# tvac_systems_interface.net
KiCad netlist of a schematic drawn in EAGLE
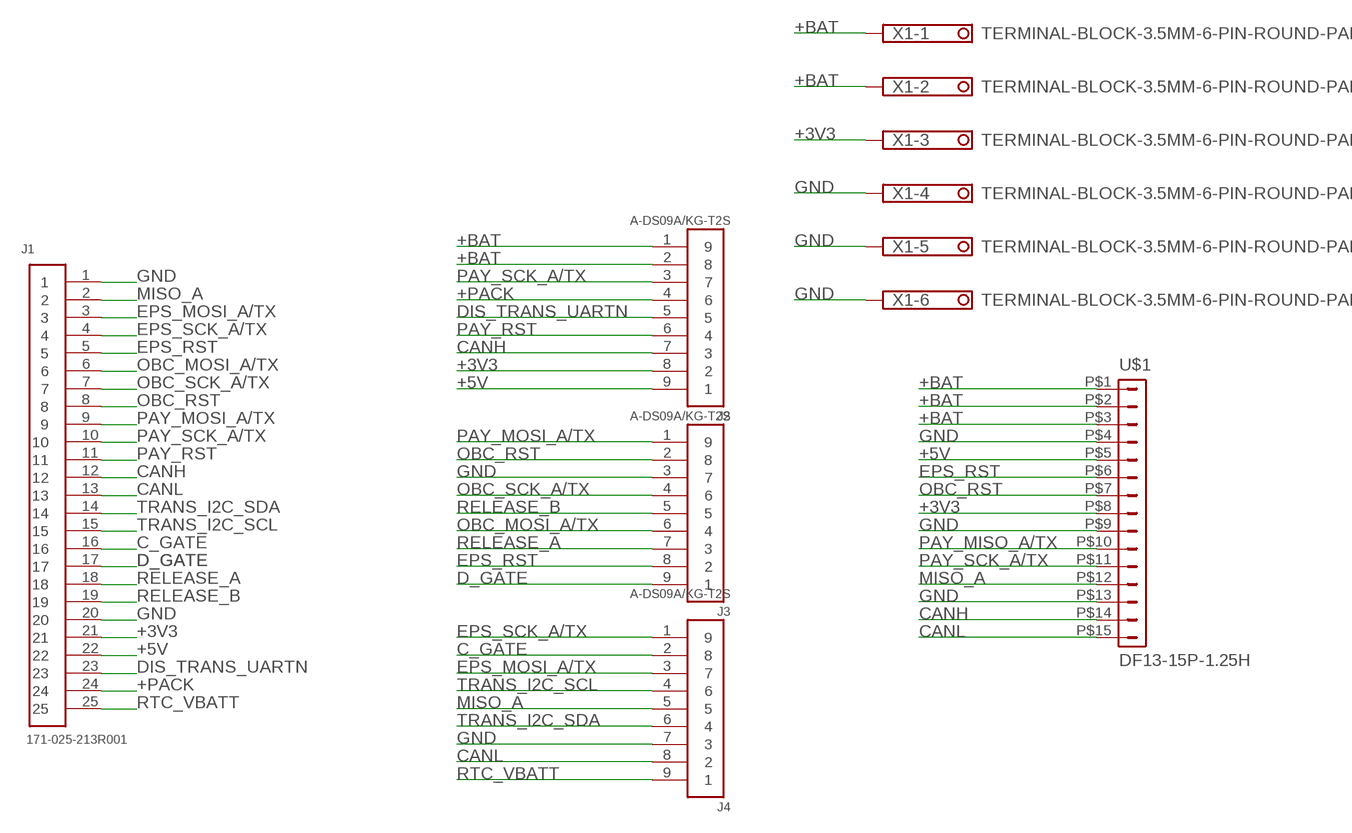
[diagram p0: schematic, sheet 1]

(export (version "E")
  (design (tool "Eeschema 10.0.6"))
  (components
    (comp (ref "J1")
      (value "171-025-213R001")
      (footprint "eagle-import:171-025-213R001")
      (fields
        (field (name "DIGIKEY_PART_NO") "4225FE-ND")
        (field (name "MANUFACTURER") "NorComp Inc.")
        (field (name "CREATED_BY") "PCBLayout.com")
      )
      (libsource (lib "eagle-import") (part "171-025-213R001"))
    )
    (comp (ref "J2")
      (value "A-DS09A/KG-T2S")
      (footprint "eagle-import:A-DS09A_KG-T2S")
      (fields
        (field (name "DIGI_KEY_PART_NUMBER") "AE10968-ND")
        (field (name "MANUFACTURER") "Assmann WSW Components")
        (field (name "MPN") "A-DS 09 A/KG-T2S")
        (field (name "CREATEDBY") "PCBLayout.com")
      )
      (libsource (lib "eagle-import") (part "A-DS09A/KG-T2S"))
    )
    (comp (ref "J3")
      (value "A-DS09A/KG-T2S")
      (footprint "eagle-import:A-DS09A_KG-T2S")
      (fields
        (field (name "DIGI_KEY_PART_NUMBER") "AE10968-ND")
        (field (name "MANUFACTURER") "Assmann WSW Components")
        (field (name "MPN") "A-DS 09 A/KG-T2S")
        (field (name "CREATEDBY") "PCBLayout.com")
      )
      (libsource (lib "eagle-import") (part "A-DS09A/KG-T2S"))
    )
    (comp (ref "J4")
      (value "A-DS09A/KG-T2S")
      (footprint "eagle-import:A-DS09A_KG-T2S")
      (fields
        (field (name "DIGI_KEY_PART_NUMBER") "AE10968-ND")
        (field (name "MANUFACTURER") "Assmann WSW Components")
        (field (name "MPN") "A-DS 09 A/KG-T2S")
        (field (name "CREATEDBY") "PCBLayout.com")
      )
      (libsource (lib "eagle-import") (part "A-DS09A/KG-T2S"))
    )
    (comp (ref "U$1")
      (value "DF13-15P-1.25H")
      (footprint "eagle-import:DF13A-15P-1.25H")
      (libsource (lib "eagle-import") (part "DF13-15P-1.25H"))
    )
    (comp (ref "X1")
      (value "TERMINAL-BLOCK-3.5MM-6-PIN-ROUND-PAD")
      (footprint "eagle-import:TERMINAL-BLOCK-6-PIN-3.5MM-ROUND-PAD")
      (libsource (lib "eagle-import") (part "TERMINAL-BLOCK-3.5MM-6-PIN-ROUND-PAD"))
    )
  )
  (nets
    (net (code "1") (name "/+3V3") (class "Default")
      (node (ref "J1") (pin "21") (pinfunction "21_21") (pintype "passive"))
      (node (ref "J2") (pin "8") (pinfunction "2_8") (pintype "passive"))
      (node (ref "U$1") (pin "P$8") (pinfunction "8_P$8") (pintype "passive"))
      (node (ref "X1") (pin "3") (pinfunction "K_3") (pintype "passive"))
    )
    (net (code "2") (name "/+5V") (class "Default")
      (node (ref "J1") (pin "22") (pinfunction "22_22") (pintype "passive"))
      (node (ref "J2") (pin "9") (pinfunction "1_9") (pintype "passive"))
      (node (ref "U$1") (pin "P$5") (pinfunction "5_P$5") (pintype "passive"))
    )
    (net (code "3") (name "/+BAT") (class "Default")
      (node (ref "J2") (pin "1") (pinfunction "9_1") (pintype "passive"))
      (node (ref "J2") (pin "2") (pinfunction "8_2") (pintype "passive"))
      (node (ref "U$1") (pin "P$1") (pinfunction "1_P$1") (pintype "passive"))
      (node (ref "U$1") (pin "P$2") (pinfunction "2_P$2") (pintype "passive"))
      (node (ref "U$1") (pin "P$3") (pinfunction "3_P$3") (pintype "passive"))
      (node (ref "X1") (pin "1") (pinfunction "K_1") (pintype "passive"))
      (node (ref "X1") (pin "2") (pinfunction "K_2") (pintype "passive"))
    )
    (net (code "4") (name "/+PACK") (class "Default")
      (node (ref "J1") (pin "24") (pinfunction "24_24") (pintype "passive"))
      (node (ref "J2") (pin "4") (pinfunction "6_4") (pintype "passive"))
    )
    (net (code "5") (name "/CANH") (class "Default")
      (node (ref "J1") (pin "12") (pinfunction "12_12") (pintype "passive"))
      (node (ref "J2") (pin "7") (pinfunction "3_7") (pintype "passive"))
      (node (ref "U$1") (pin "P$14") (pinfunction "14_P$14") (pintype "passive"))
    )
    (net (code "6") (name "/CANL") (class "Default")
      (node (ref "J1") (pin "13") (pinfunction "13_13") (pintype "passive"))
      (node (ref "J4") (pin "8") (pinfunction "2_8") (pintype "passive"))
      (node (ref "U$1") (pin "P$15") (pinfunction "15_P$15") (pintype "passive"))
    )
    (net (code "7") (name "/C_GATE") (class "Default")
      (node (ref "J1") (pin "16") (pinfunction "16_16") (pintype "passive"))
      (node (ref "J4") (pin "2") (pinfunction "8_2") (pintype "passive"))
    )
    (net (code "8") (name "/DIS_TRANS_UARTN") (class "Default")
      (node (ref "J1") (pin "23") (pinfunction "23_23") (pintype "passive"))
      (node (ref "J2") (pin "5") (pinfunction "5_5") (pintype "passive"))
    )
    (net (code "9") (name "/D_GATE") (class "Default")
      (node (ref "J1") (pin "17") (pinfunction "17_17") (pintype "passive"))
      (node (ref "J3") (pin "9") (pinfunction "1_9") (pintype "passive"))
    )
    (net (code "10") (name "/EPS_MOSI_A{slash}TX") (class "Default")
      (node (ref "J1") (pin "3") (pinfunction "3_3") (pintype "passive"))
      (node (ref "J4") (pin "3") (pinfunction "7_3") (pintype "passive"))
    )
    (net (code "11") (name "/EPS_RST") (class "Default")
      (node (ref "J1") (pin "5") (pinfunction "5_5") (pintype "passive"))
      (node (ref "J3") (pin "8") (pinfunction "2_8") (pintype "passive"))
      (node (ref "U$1") (pin "P$6") (pinfunction "6_P$6") (pintype "passive"))
    )
    (net (code "12") (name "/EPS_SCK_A{slash}TX") (class "Default")
      (node (ref "J1") (pin "4") (pinfunction "4_4") (pintype "passive"))
      (node (ref "J4") (pin "1") (pinfunction "9_1") (pintype "passive"))
    )
    (net (code "13") (name "/GND") (class "Default")
      (node (ref "J1") (pin "1") (pinfunction "1_1") (pintype "passive"))
      (node (ref "J1") (pin "20") (pinfunction "20_20") (pintype "passive"))
      (node (ref "J3") (pin "3") (pinfunction "7_3") (pintype "passive"))
      (node (ref "J4") (pin "7") (pinfunction "3_7") (pintype "passive"))
      (node (ref "U$1") (pin "P$13") (pinfunction "13_P$13") (pintype "passive"))
      (node (ref "U$1") (pin "P$4") (pinfunction "4_P$4") (pintype "passive"))
      (node (ref "U$1") (pin "P$9") (pinfunction "9_P$9") (pintype "passive"))
      (node (ref "X1") (pin "4") (pinfunction "K_4") (pintype "passive"))
      (node (ref "X1") (pin "5") (pinfunction "K_5") (pintype "passive"))
      (node (ref "X1") (pin "6") (pinfunction "K_6") (pintype "passive"))
    )
    (net (code "14") (name "/MISO_A") (class "Default")
      (node (ref "J1") (pin "2") (pinfunction "2_2") (pintype "passive"))
      (node (ref "J4") (pin "5") (pinfunction "5_5") (pintype "passive"))
      (node (ref "U$1") (pin "P$12") (pinfunction "12_P$12") (pintype "passive"))
    )
    (net (code "15") (name "/OBC_MOSI_A{slash}TX") (class "Default")
      (node (ref "J1") (pin "6") (pinfunction "6_6") (pintype "passive"))
      (node (ref "J3") (pin "6") (pinfunction "4_6") (pintype "passive"))
    )
    (net (code "16") (name "/OBC_RST") (class "Default")
      (node (ref "J1") (pin "8") (pinfunction "8_8") (pintype "passive"))
      (node (ref "J3") (pin "2") (pinfunction "8_2") (pintype "passive"))
      (node (ref "U$1") (pin "P$7") (pinfunction "7_P$7") (pintype "passive"))
    )
    (net (code "17") (name "/OBC_SCK_A{slash}TX") (class "Default")
      (node (ref "J1") (pin "7") (pinfunction "7_7") (pintype "passive"))
      (node (ref "J3") (pin "4") (pinfunction "6_4") (pintype "passive"))
    )
    (net (code "18") (name "/PAY_MISO_A{slash}TX") (class "Default")
      (node (ref "U$1") (pin "P$10") (pinfunction "10_P$10") (pintype "passive"))
    )
    (net (code "19") (name "/PAY_MOSI_A{slash}TX") (class "Default")
      (node (ref "J1") (pin "9") (pinfunction "9_9") (pintype "passive"))
      (node (ref "J3") (pin "1") (pinfunction "9_1") (pintype "passive"))
    )
    (net (code "20") (name "/PAY_RST") (class "Default")
      (node (ref "J1") (pin "11") (pinfunction "11_11") (pintype "passive"))
      (node (ref "J2") (pin "6") (pinfunction "4_6") (pintype "passive"))
    )
    (net (code "21") (name "/PAY_SCK_A{slash}TX") (class "Default")
      (node (ref "J1") (pin "10") (pinfunction "10_10") (pintype "passive"))
      (node (ref "J2") (pin "3") (pinfunction "7_3") (pintype "passive"))
      (node (ref "U$1") (pin "P$11") (pinfunction "11_P$11") (pintype "passive"))
    )
    (net (code "22") (name "/RELEASE_A") (class "Default")
      (node (ref "J1") (pin "18") (pinfunction "18_18") (pintype "passive"))
      (node (ref "J3") (pin "7") (pinfunction "3_7") (pintype "passive"))
    )
    (net (code "23") (name "/RELEASE_B") (class "Default")
      (node (ref "J1") (pin "19") (pinfunction "19_19") (pintype "passive"))
      (node (ref "J3") (pin "5") (pinfunction "5_5") (pintype "passive"))
    )
    (net (code "24") (name "/RTC_VBATT") (class "Default")
      (node (ref "J1") (pin "25") (pinfunction "25_25") (pintype "passive"))
      (node (ref "J4") (pin "9") (pinfunction "1_9") (pintype "passive"))
    )
    (net (code "25") (name "/TRANS_I2C_SCL") (class "Default")
      (node (ref "J1") (pin "15") (pinfunction "15_15") (pintype "passive"))
      (node (ref "J4") (pin "4") (pinfunction "6_4") (pintype "passive"))
    )
    (net (code "26") (name "/TRANS_I2C_SDA") (class "Default")
      (node (ref "J1") (pin "14") (pinfunction "14_14") (pintype "passive"))
      (node (ref "J4") (pin "6") (pinfunction "4_6") (pintype "passive"))
    )
  )
)
